# Arduino_Zero.net
KiCad netlist of a schematic drawn in EAGLE
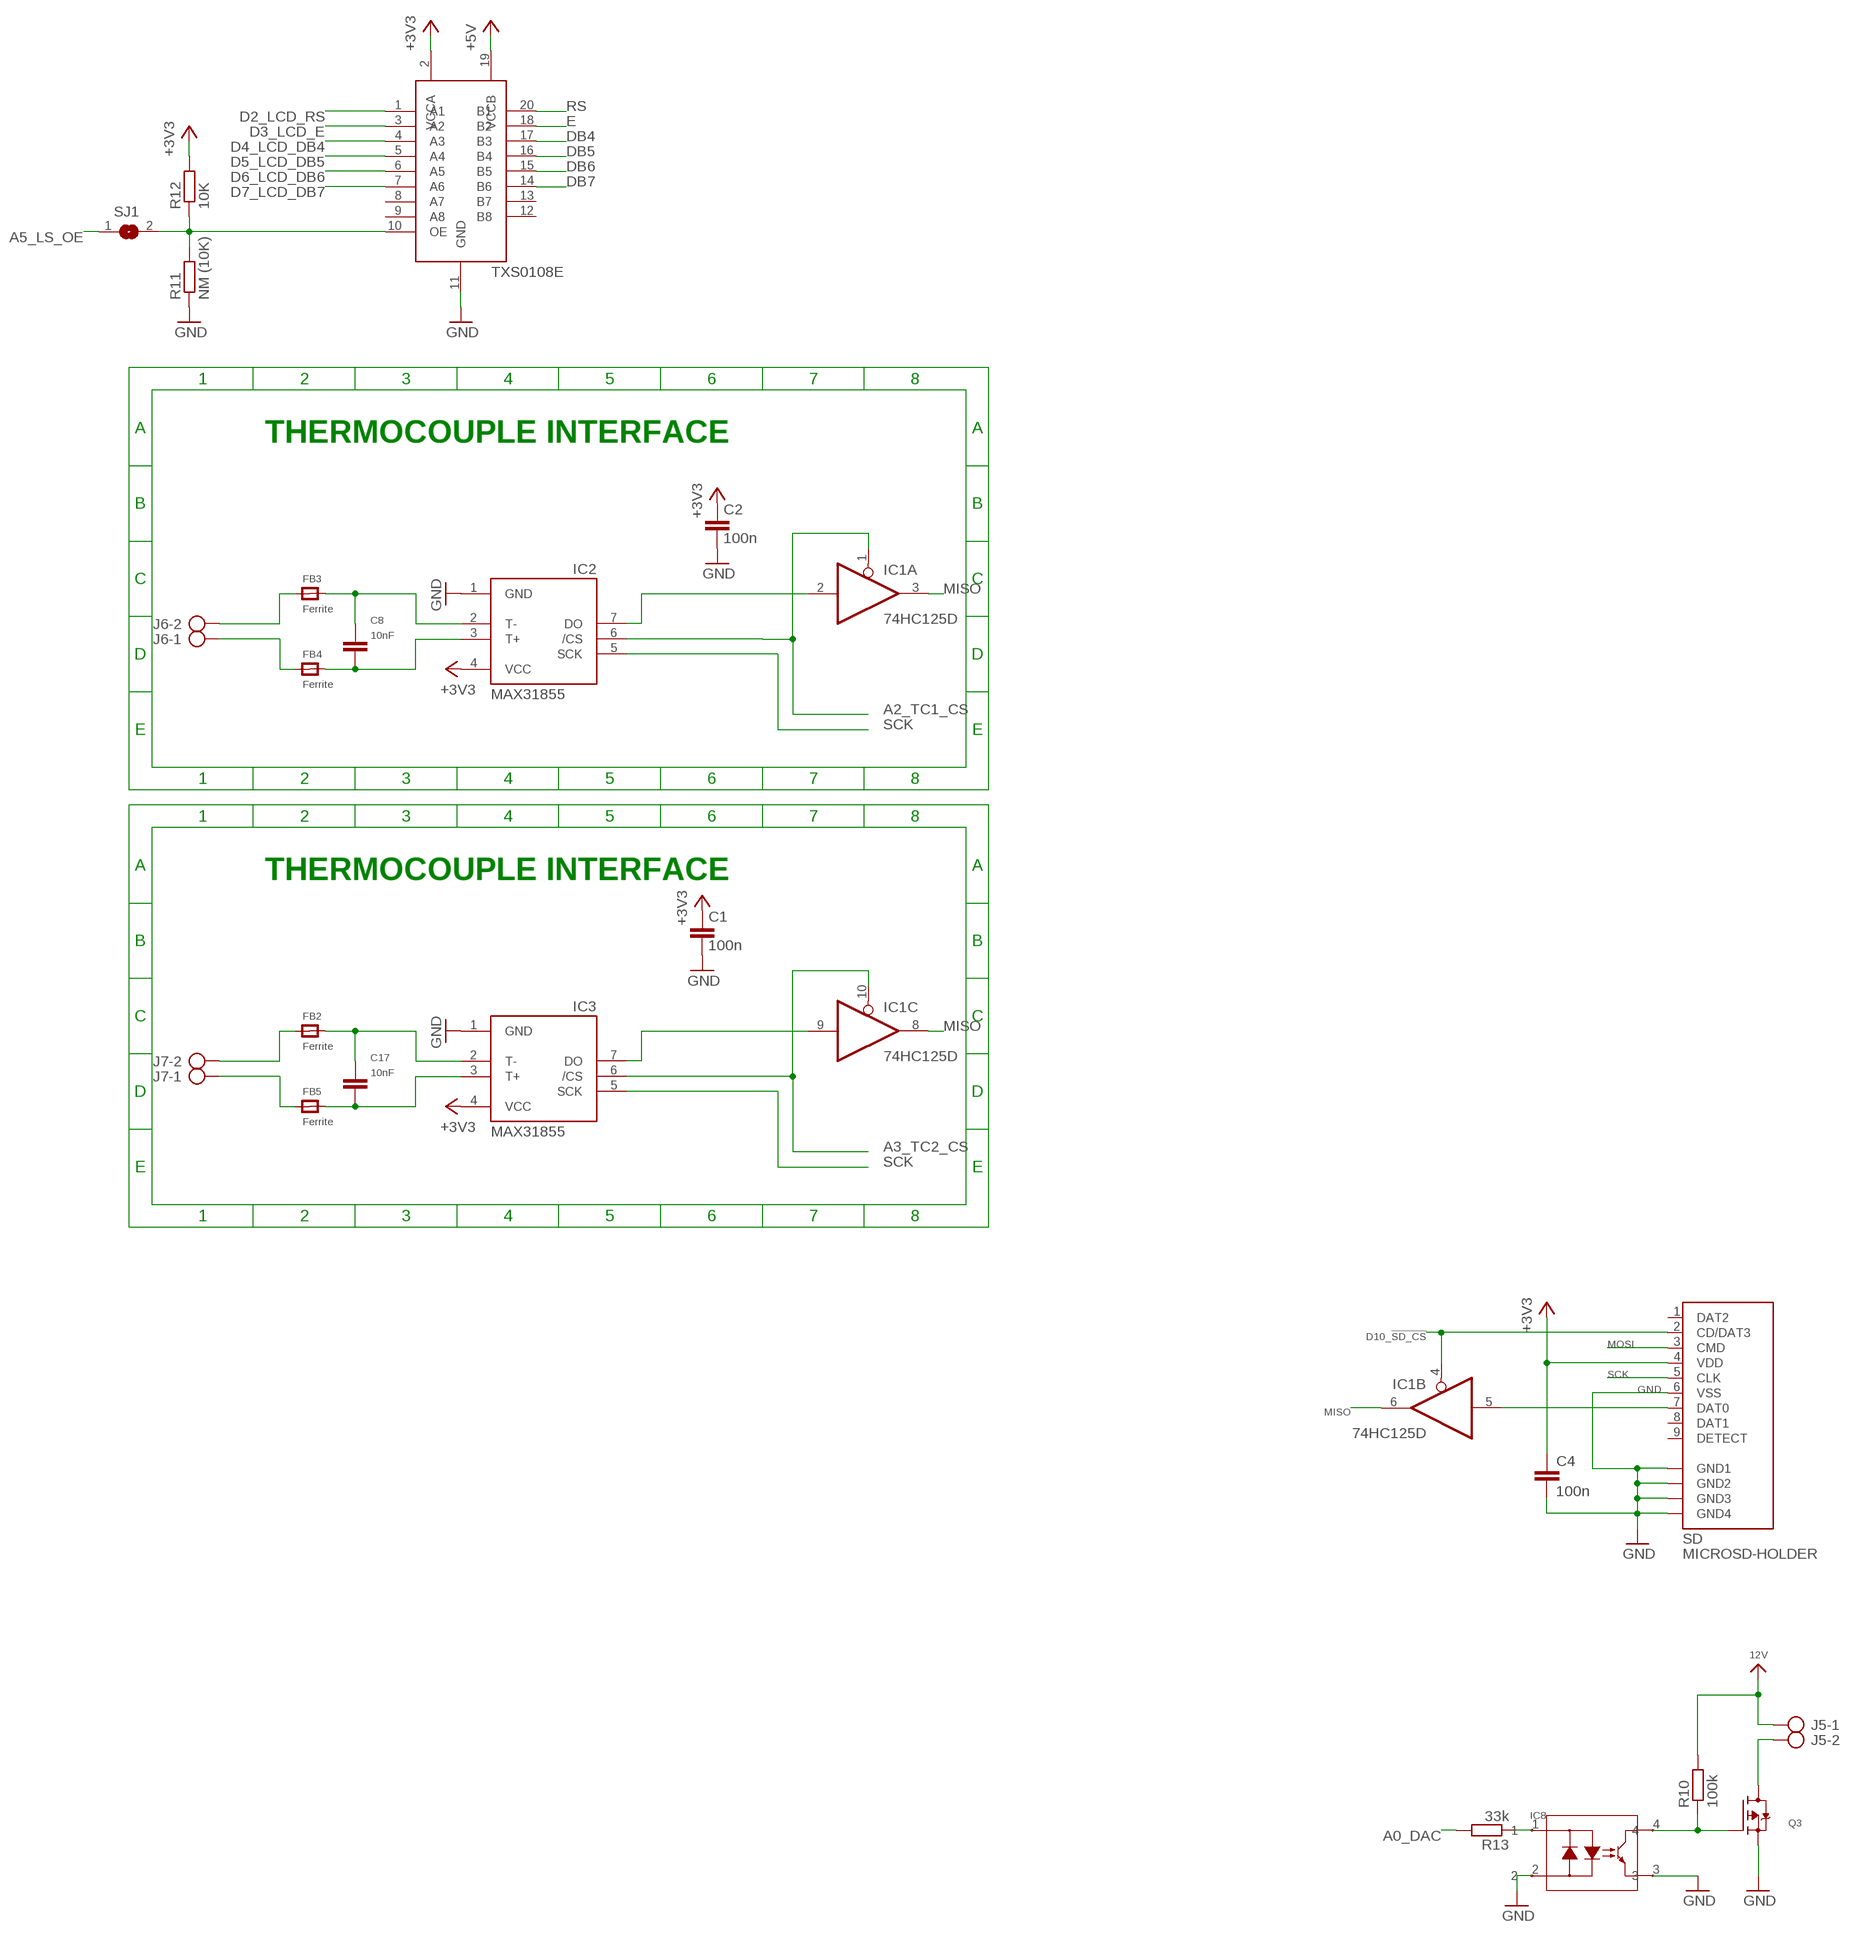
[diagram p0: schematic, sheet 1, part 1 of 2]
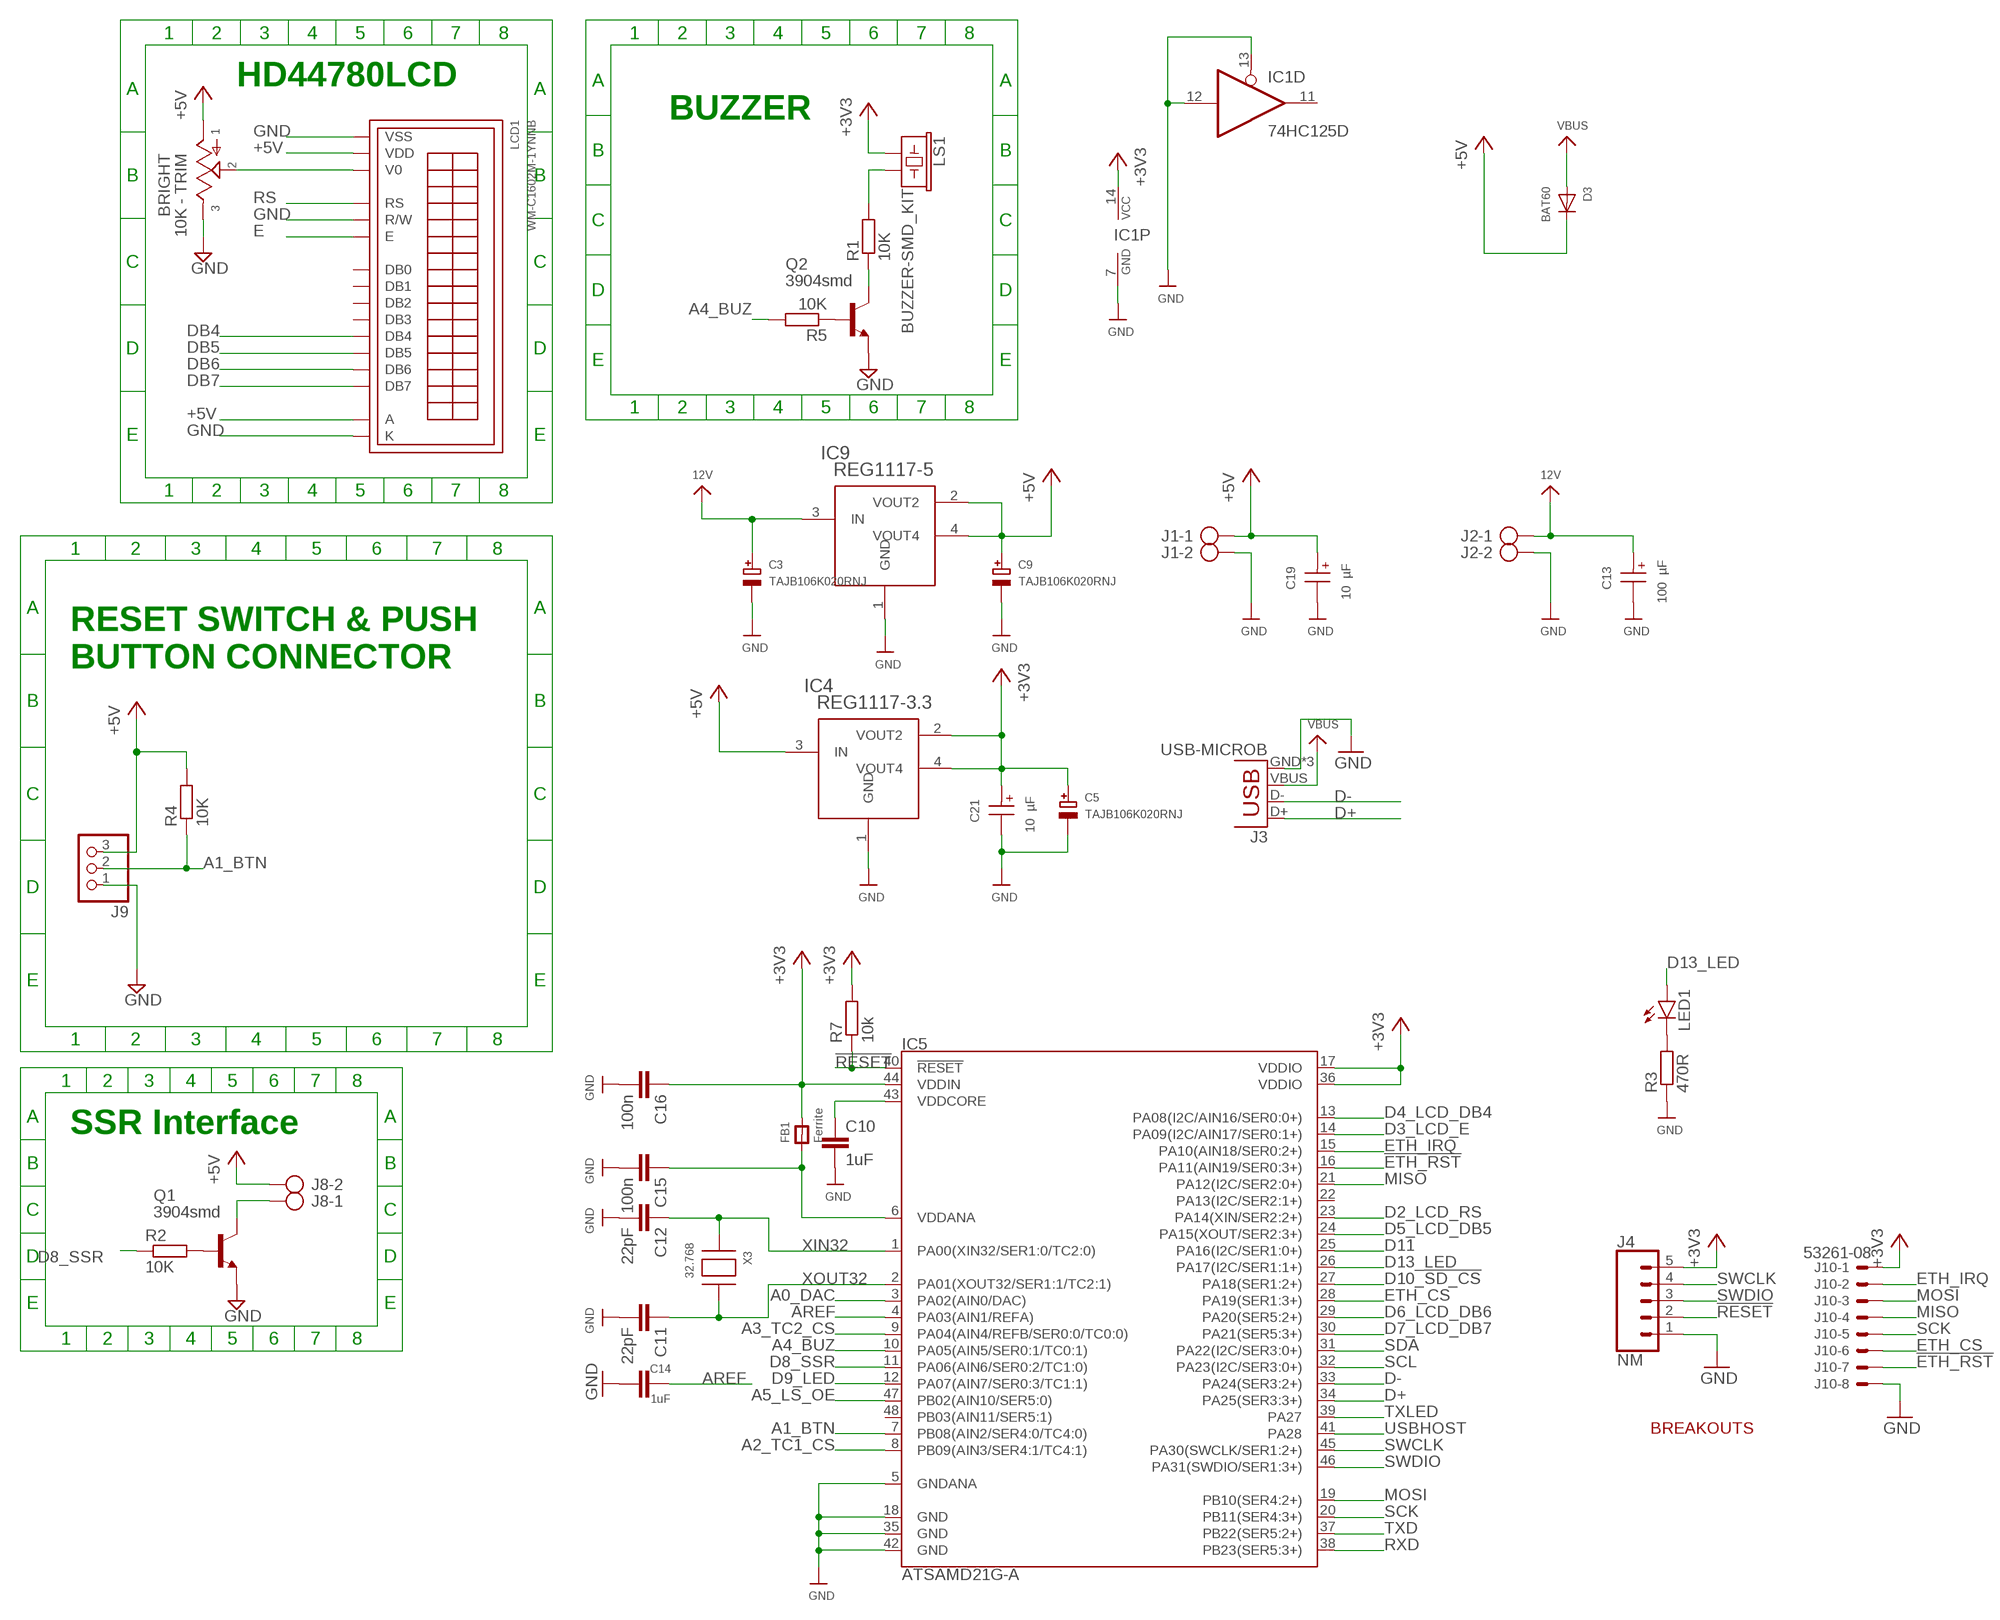
[diagram p1: schematic, sheet 1, part 2 of 2]

(export (version "E")
  (design (tool "Eeschema 10.0.6"))
  (components
    (comp (ref "BRIGHT")
      (value "10K - TRIM")
      (footprint "eagle-import:B25P")
      (libsource (lib "eagle-import") (part "POTTRIM"))
    )
    (comp (ref "C1")
      (value "100n")
      (footprint "eagle-import:C0603K")
      (libsource (lib "eagle-import") (part "C-EUC0603K"))
    )
    (comp (ref "C2")
      (value "100n")
      (footprint "eagle-import:C0603K")
      (libsource (lib "eagle-import") (part "C-EUC0603K"))
    )
    (comp (ref "C3")
      (value "TAJB106K020RNJ")
      (footprint "eagle-import:CAPMP3528X210N")
      (libsource (lib "eagle-import") (part "CAP_TANTALUM"))
    )
    (comp (ref "C4")
      (value "100n")
      (footprint "eagle-import:C0603K")
      (libsource (lib "eagle-import") (part "C-EUC0603K"))
    )
    (comp (ref "C5")
      (value "TAJB106K020RNJ")
      (footprint "eagle-import:CAPMP3528X210N")
      (libsource (lib "eagle-import") (part "CAP_TANTALUM"))
    )
    (comp (ref "C8")
      (value "10nF")
      (footprint "eagle-import:C0603K")
      (libsource (lib "eagle-import") (part "C-EUC0603K"))
    )
    (comp (ref "C9")
      (value "TAJB106K020RNJ")
      (footprint "eagle-import:CAPMP3528X210N")
      (libsource (lib "eagle-import") (part "CAP_TANTALUM"))
    )
    (comp (ref "C10")
      (value "1uF")
      (footprint "eagle-import:C0603K")
      (libsource (lib "eagle-import") (part "C-EUC0603K"))
    )
    (comp (ref "C11")
      (value "22pF")
      (footprint "eagle-import:C0603K")
      (libsource (lib "eagle-import") (part "C-EUC0603K"))
    )
    (comp (ref "C12")
      (value "22pF")
      (footprint "eagle-import:C0603K")
      (libsource (lib "eagle-import") (part "C-EUC0603K"))
    )
    (comp (ref "C13")
      (value "100 µF")
      (footprint "eagle-import:WCAP-ASLI_6.3X7.7(DXL)")
      (libsource (lib "eagle-import") (part "WCAP-ASLI_6.3X7.7_865080545012"))
    )
    (comp (ref "C14")
      (value "1uF")
      (footprint "eagle-import:C0603K")
      (libsource (lib "eagle-import") (part "C-EUC0603K"))
    )
    (comp (ref "C15")
      (value "100n")
      (footprint "eagle-import:C0603K")
      (libsource (lib "eagle-import") (part "C-EUC0603K"))
    )
    (comp (ref "C16")
      (value "100n")
      (footprint "eagle-import:C0603K")
      (libsource (lib "eagle-import") (part "C-EUC0603K"))
    )
    (comp (ref "C17")
      (value "10nF")
      (footprint "eagle-import:C0603K")
      (libsource (lib "eagle-import") (part "C-EUC0603K"))
    )
    (comp (ref "C19")
      (value "10 µF")
      (footprint "eagle-import:WCAP-ASLI_4X5.5(DXL)")
      (libsource (lib "eagle-import") (part "WCAP-ASLI_4X5.5_865080340001"))
    )
    (comp (ref "C21")
      (value "10 µF")
      (footprint "eagle-import:WCAP-ASLI_4X5.5(DXL)")
      (libsource (lib "eagle-import") (part "WCAP-ASLI_4X5.5_865080340001"))
    )
    (comp (ref "D3")
      (value "BAT60")
      (footprint "eagle-import:SOD323")
      (libsource (lib "eagle-import") (part "DIODESOD-323-3D"))
    )
    (comp (ref "FB1")
      (value "Ferrite")
      (footprint "eagle-import:BEADC3216X100N")
      (libsource (lib "eagle-import") (part "FERRITEBEAD"))
    )
    (comp (ref "FB2")
      (value "Ferrite")
      (footprint "eagle-import:BEADC3216X100N")
      (libsource (lib "eagle-import") (part "FERRITEBEAD"))
    )
    (comp (ref "FB3")
      (value "Ferrite")
      (footprint "eagle-import:BEADC3216X100N")
      (libsource (lib "eagle-import") (part "FERRITEBEAD"))
    )
    (comp (ref "FB4")
      (value "Ferrite")
      (footprint "eagle-import:BEADC3216X100N")
      (libsource (lib "eagle-import") (part "FERRITEBEAD"))
    )
    (comp (ref "FB5")
      (value "Ferrite")
      (footprint "eagle-import:BEADC3216X100N")
      (libsource (lib "eagle-import") (part "FERRITEBEAD"))
    )
    (comp (ref "IC1")
      (value "74HC125D")
      (footprint "eagle-import:SO14")
      (libsource (lib "eagle-import") (part "74125DHC"))
    )
    (comp (ref "IC2")
      (value "MAX31855")
      (footprint "eagle-import:SO08")
      (libsource (lib "eagle-import") (part "MAX6675"))
    )
    (comp (ref "IC3")
      (value "MAX31855")
      (footprint "eagle-import:SO08")
      (libsource (lib "eagle-import") (part "MAX6675"))
    )
    (comp (ref "IC4")
      (value "REG1117-3.3")
      (footprint "eagle-import:DCY0004A_N")
      (fields
        (field (name "MANUFACTURER_PART_NUMBER") "TLV1117-33CDCYR")
        (field (name "COPYRIGHT") "Copyright (C) 2022 Ultra Librarian. All rights reserved.")
      )
      (libsource (lib "eagle-import") (part "REG1117-5"))
    )
    (comp (ref "IC5")
      (value "ATSAMD21G-A")
      (footprint "eagle-import:TQFP-48")
      (libsource (lib "eagle-import") (part "ATSAMD21G-A"))
    )
    (comp (ref "IC7")
      (value "TXS0108E")
      (footprint "eagle-import:TSSOP20")
      (libsource (lib "eagle-import") (part "TXS0108E"))
    )
    (comp (ref "IC8")
      (value "TLP283")
      (footprint "eagle-import:SO4_TOS")
      (fields
        (field (name "MANUFACTURER_PART_NUMBER") "TLP292")
        (field (name "COPYRIGHT") "Copyright (C) 2022 Ultra Librarian. All rights reserved.")
      )
      (libsource (lib "eagle-import") (part "TLP292"))
    )
    (comp (ref "IC9")
      (value "REG1117-5")
      (footprint "eagle-import:DCY0004A_N")
      (fields
        (field (name "MANUFACTURER_PART_NUMBER") "TLV1117-33CDCYR")
        (field (name "COPYRIGHT") "Copyright (C) 2022 Ultra Librarian. All rights reserved.")
      )
      (libsource (lib "eagle-import") (part "REG1117-5"))
    )
    (comp (ref "J1")
      (value "AK500/2ASD")
      (footprint "eagle-import:AK500_2")
      (libsource (lib "eagle-import") (part "AK500/2ASD"))
    )
    (comp (ref "J2")
      (value "AK500/2ASD")
      (footprint "eagle-import:AK500_2")
      (libsource (lib "eagle-import") (part "AK500/2ASD"))
    )
    (comp (ref "J3")
      (value "USB-MICROB")
      (footprint "eagle-import:USB-MICROB")
      (libsource (lib "eagle-import") (part "USB-MICROB"))
    )
    (comp (ref "J4")
      (value "NM")
      (footprint "eagle-import:1X05_1.27MM")
      (libsource (lib "eagle-import") (part "CONN_051.27MM"))
    )
    (comp (ref "J5")
      (value "AK500/2ASD")
      (footprint "eagle-import:AK500_2")
      (libsource (lib "eagle-import") (part "AK500/2ASD"))
    )
    (comp (ref "J6")
      (value "AK500/2ASD")
      (footprint "eagle-import:AK500_2")
      (libsource (lib "eagle-import") (part "AK500/2ASD"))
    )
    (comp (ref "J7")
      (value "AK500/2ASD")
      (footprint "eagle-import:AK500_2")
      (libsource (lib "eagle-import") (part "AK500/2ASD"))
    )
    (comp (ref "J8")
      (value "AK500/2ASD")
      (footprint "eagle-import:AK500_2")
      (libsource (lib "eagle-import") (part "AK500/2ASD"))
    )
    (comp (ref "J9")
      (value "PINHD-1X3")
      (footprint "eagle-import:1X03")
      (libsource (lib "eagle-import") (part "PINHD-1X3"))
    )
    (comp (ref "J10")
      (value "53261-08")
      (footprint "eagle-import:53261-08")
      (fields (field (name "MF") "MOLEX"))
      (libsource (lib "eagle-import") (part "53?-08261"))
    )
    (comp (ref "LCD1")
      (value "WM-C1602M-1YNNB")
      (footprint "eagle-import:LCD_2")
      (libsource (lib "eagle-import") (part "WM-C1602M-1YNNB"))
    )
    (comp (ref "LED1")
      (value "LEDCHIPLED_0805")
      (footprint "eagle-import:CHIPLED_0805")
      (libsource (lib "eagle-import") (part "LEDCHIPLED_0805"))
    )
    (comp (ref "LS1")
      (value "BUZZER-SMD_KIT")
      (footprint "eagle-import:BUZZER-CCV-KIT")
      (libsource (lib "eagle-import") (part "BUZZER-SMD_KIT"))
    )
    (comp (ref "Q1")
      (value "3904smd")
      (footprint "eagle-import:SOT23-BEC")
      (libsource (lib "eagle-import") (part "BC850SMD"))
    )
    (comp (ref "Q2")
      (value "3904smd")
      (footprint "eagle-import:SOT23-BEC")
      (libsource (lib "eagle-import") (part "BC850SMD"))
    )
    (comp (ref "Q3")
      (value "MOSFET-PWIDE")
      (footprint "eagle-import:SOT23-WIDE")
      (libsource (lib "eagle-import") (part "MOSFET-PWIDE"))
    )
    (comp (ref "R1")
      (value "10K")
      (footprint "eagle-import:R0603")
      (libsource (lib "eagle-import") (part "R-EU_R0603"))
    )
    (comp (ref "R2")
      (value "10K")
      (footprint "eagle-import:R0603")
      (libsource (lib "eagle-import") (part "R-EU_R0603"))
    )
    (comp (ref "R3")
      (value "470R")
      (footprint "eagle-import:R0603")
      (libsource (lib "eagle-import") (part "R-EU_R0603"))
    )
    (comp (ref "R4")
      (value "10K")
      (footprint "eagle-import:R0603")
      (libsource (lib "eagle-import") (part "R-EU_R0603"))
    )
    (comp (ref "R5")
      (value "10K")
      (footprint "eagle-import:R0603")
      (libsource (lib "eagle-import") (part "R-EU_R0603"))
    )
    (comp (ref "R7")
      (value "10k")
      (footprint "eagle-import:R0603")
      (libsource (lib "eagle-import") (part "R-EU_R0603"))
    )
    (comp (ref "R10")
      (value "100k")
      (footprint "eagle-import:R0603")
      (libsource (lib "eagle-import") (part "R-EU_R0603"))
    )
    (comp (ref "R11")
      (value "NM (10K)")
      (footprint "eagle-import:R0603")
      (libsource (lib "eagle-import") (part "R-EU_R0603"))
    )
    (comp (ref "R12")
      (value "10K")
      (footprint "eagle-import:R0603")
      (libsource (lib "eagle-import") (part "R-EU_R0603"))
    )
    (comp (ref "R13")
      (value "33k")
      (footprint "eagle-import:R0603")
      (libsource (lib "eagle-import") (part "R-EU_R0603"))
    )
    (comp (ref "SD")
      (value "MICROSD-HOLDER")
      (footprint "eagle-import:MICROSD-HOLDER-ALIEX")
      (libsource (lib "eagle-import") (part "MICROSD-HOLDER"))
    )
    (comp (ref "SJ1") (value "SJ") (footprint "eagle-import:SJ") (libsource (lib "eagle-import") (part "SJ")))
    (comp (ref "X3")
      (value "32.768")
      (footprint "eagle-import:XTAL3215")
      (libsource (lib "eagle-import") (part "XTAL-3.2X1.5"))
    )
  )
  (nets
    (net (code "1") (name "+3V3") (class "Default")
      (node (ref "C1") (pin "1") (pinfunction "1_1") (pintype "passive"))
      (node (ref "C16") (pin "1") (pinfunction "1_1") (pintype "passive"))
      (node (ref "C2") (pin "1") (pinfunction "1_1") (pintype "passive"))
      (node (ref "C21") (pin "1") (pinfunction "+_1") (pintype "passive"))
      (node (ref "C4") (pin "1") (pinfunction "1_1") (pintype "passive"))
      (node (ref "C5") (pin "1") (pinfunction "+_1") (pintype "passive"))
      (node (ref "FB1") (pin "2") (pinfunction "P$2_2") (pintype "passive"))
      (node (ref "IC1") (pin "14") (pinfunction "VCC_14") (pintype "power_in"))
      (node (ref "IC2") (pin "4") (pinfunction "VCC_4") (pintype "power_in"))
      (node (ref "IC3") (pin "4") (pinfunction "VCC_4") (pintype "power_in"))
      (node (ref "IC4") (pin "2") (pinfunction "VOUT2_2") (pintype "power_in"))
      (node (ref "IC4") (pin "4") (pinfunction "VOUT4_4") (pintype "power_in"))
      (node (ref "IC5") (pin "17") (pinfunction "VDDIO_17") (pintype "bidirectional"))
      (node (ref "IC5") (pin "36") (pinfunction "VDDIO_36") (pintype "bidirectional"))
      (node (ref "IC5") (pin "44") (pinfunction "VDDIN_44") (pintype "bidirectional"))
      (node (ref "IC7") (pin "2") (pinfunction "VCCA_2") (pintype "bidirectional"))
      (node (ref "J10") (pin "1") (pinfunction "S_1") (pintype "passive"))
      (node (ref "J4") (pin "5") (pinfunction "5_5") (pintype "passive"))
      (node (ref "LS1") (pin "+") (pinfunction "1_+") (pintype "passive"))
      (node (ref "R12") (pin "2") (pinfunction "2_2") (pintype "passive"))
      (node (ref "R7") (pin "2") (pinfunction "2_2") (pintype "passive"))
      (node (ref "SD") (pin "4") (pinfunction "VDD_4") (pintype "bidirectional"))
    )
    (net (code "2") (name "+5V") (class "Default")
      (node (ref "BRIGHT") (pin "1") (pinfunction "1_1") (pintype "passive"))
      (node (ref "C19") (pin "1") (pinfunction "+_1") (pintype "passive"))
      (node (ref "C9") (pin "1") (pinfunction "+_1") (pintype "passive"))
      (node (ref "D3") (pin "1") (pinfunction "C_1") (pintype "passive"))
      (node (ref "IC4") (pin "3") (pinfunction "IN_3") (pintype "power_in"))
      (node (ref "IC7") (pin "19") (pinfunction "VCCB_19") (pintype "bidirectional"))
      (node (ref "IC9") (pin "2") (pinfunction "VOUT2_2") (pintype "power_in"))
      (node (ref "IC9") (pin "4") (pinfunction "VOUT4_4") (pintype "power_in"))
      (node (ref "J1") (pin "1") (pinfunction "KL_1") (pintype "passive"))
      (node (ref "J8") (pin "2") (pinfunction "KL_2") (pintype "passive"))
      (node (ref "J9") (pin "3") (pinfunction "3_3") (pintype "passive"))
      (node (ref "LCD1") (pin "15") (pinfunction "A_15") (pintype "bidirectional"))
      (node (ref "LCD1") (pin "2") (pinfunction "VDD_2") (pintype "bidirectional"))
      (node (ref "R4") (pin "2") (pinfunction "2_2") (pintype "passive"))
    )
    (net (code "3") (name "/A0_DAC") (class "Default")
      (node (ref "IC5") (pin "3") (pinfunction "PA02(AIN0/DAC)_3") (pintype "bidirectional"))
      (node (ref "R13") (pin "2") (pinfunction "2_2") (pintype "passive"))
    )
    (net (code "4") (name "/A1_BTN") (class "Default")
      (node (ref "IC5") (pin "7") (pinfunction "PB08(AIN2/SER4:0/TC4:0)_7") (pintype "bidirectional"))
      (node (ref "J9") (pin "2") (pinfunction "2_2") (pintype "passive"))
      (node (ref "R4") (pin "1") (pinfunction "1_1") (pintype "passive"))
    )
    (net (code "5") (name "/A2_TC1_CS") (class "Default")
      (node (ref "IC1") (pin "1") (pinfunction "OE_1") (pintype "input"))
      (node (ref "IC2") (pin "6") (pinfunction "/CS_6") (pintype "input"))
      (node (ref "IC5") (pin "8") (pinfunction "PB09(AIN3/SER4:1/TC4:1)_8") (pintype "bidirectional"))
    )
    (net (code "6") (name "/A3_TC2_CS") (class "Default")
      (node (ref "IC1") (pin "10") (pinfunction "OE_10") (pintype "input"))
      (node (ref "IC3") (pin "6") (pinfunction "/CS_6") (pintype "input"))
      (node (ref "IC5") (pin "9") (pinfunction "PA04(AIN4/REFB/SER0:0/TC0:0)_9") (pintype "bidirectional"))
    )
    (net (code "7") (name "/A4_BUZ") (class "Default")
      (node (ref "IC5") (pin "10") (pinfunction "PA05(AIN5/SER0:1/TC0:1)_10") (pintype "bidirectional"))
      (node (ref "R5") (pin "2") (pinfunction "2_2") (pintype "passive"))
    )
    (net (code "8") (name "/A5_LS_OE") (class "Default")
      (node (ref "IC5") (pin "47") (pinfunction "PB02(AIN10/SER5:0)_47") (pintype "bidirectional"))
      (node (ref "SJ1") (pin "1") (pinfunction "1_1") (pintype "passive"))
    )
    (net (code "9") (name "/AREF") (class "Default")
      (node (ref "C14") (pin "1") (pinfunction "1_1") (pintype "passive"))
      (node (ref "IC5") (pin "4") (pinfunction "PA03(AIN1/REFA)_4") (pintype "bidirectional"))
    )
    (net (code "10") (name "/D+") (class "Default")
      (node (ref "IC5") (pin "34") (pinfunction "PA25(SER3:3+)_34") (pintype "bidirectional"))
      (node (ref "J3") (pin "D+") (pinfunction "D+_D+") (pintype "bidirectional"))
    )
    (net (code "11") (name "/D-") (class "Default")
      (node (ref "IC5") (pin "33") (pinfunction "PA24(SER3:2+)_33") (pintype "bidirectional"))
      (node (ref "J3") (pin "D-") (pinfunction "D-_D-") (pintype "bidirectional"))
    )
    (net (code "12") (name "/D2_LCD_RS") (class "Default")
      (node (ref "IC5") (pin "23") (pinfunction "PA14(XIN/SER2:2+)_23") (pintype "bidirectional"))
      (node (ref "IC7") (pin "1") (pinfunction "A1_1") (pintype "bidirectional"))
    )
    (net (code "13") (name "/D3_LCD_E") (class "Default")
      (node (ref "IC5") (pin "14") (pinfunction "PA09(I2C/AIN17/SER0:1+)_14") (pintype "bidirectional"))
      (node (ref "IC7") (pin "3") (pinfunction "A2_3") (pintype "bidirectional"))
    )
    (net (code "14") (name "/D4_LCD_DB4") (class "Default")
      (node (ref "IC5") (pin "13") (pinfunction "PA08(I2C/AIN16/SER0:0+)_13") (pintype "bidirectional"))
      (node (ref "IC7") (pin "4") (pinfunction "A3_4") (pintype "bidirectional"))
    )
    (net (code "15") (name "/D5_LCD_DB5") (class "Default")
      (node (ref "IC5") (pin "24") (pinfunction "PA15(XOUT/SER2:3+)_24") (pintype "bidirectional"))
      (node (ref "IC7") (pin "5") (pinfunction "A4_5") (pintype "bidirectional"))
    )
    (net (code "16") (name "/D6_LCD_DB6") (class "Default")
      (node (ref "IC5") (pin "29") (pinfunction "PA20(SER5:2+)_29") (pintype "bidirectional"))
      (node (ref "IC7") (pin "6") (pinfunction "A5_6") (pintype "bidirectional"))
    )
    (net (code "17") (name "/D7_LCD_DB7") (class "Default")
      (node (ref "IC5") (pin "30") (pinfunction "PA21(SER5:3+)_30") (pintype "bidirectional"))
      (node (ref "IC7") (pin "7") (pinfunction "A6_7") (pintype "bidirectional"))
    )
    (net (code "18") (name "/D8_SSR") (class "Default")
      (node (ref "IC5") (pin "11") (pinfunction "PA06(AIN6/SER0:2/TC1:0)_11") (pintype "bidirectional"))
      (node (ref "R2") (pin "1") (pinfunction "1_1") (pintype "passive"))
    )
    (net (code "19") (name "/D9_LED") (class "Default")
      (node (ref "IC5") (pin "12") (pinfunction "PA07(AIN7/SER0:3/TC1:1)_12") (pintype "bidirectional"))
    )
    (net (code "20") (name "/D10_~{SD_CS}") (class "Default")
      (node (ref "IC1") (pin "4") (pinfunction "OE_4") (pintype "input"))
      (node (ref "IC5") (pin "27") (pinfunction "PA18(SER1:2+)_27") (pintype "bidirectional"))
      (node (ref "SD") (pin "2") (pinfunction "CD/DAT3_2") (pintype "bidirectional"))
    )
    (net (code "21") (name "/D11") (class "Default")
      (node (ref "IC5") (pin "25") (pinfunction "PA16(I2C/SER1:0+)_25") (pintype "bidirectional"))
    )
    (net (code "22") (name "/D13_LED") (class "Default")
      (node (ref "IC5") (pin "26") (pinfunction "PA17(I2C/SER1:1+)_26") (pintype "bidirectional"))
      (node (ref "LED1") (pin "A") (pinfunction "A_A") (pintype "passive"))
    )
    (net (code "23") (name "/DB4") (class "Default")
      (node (ref "IC7") (pin "17") (pinfunction "B3_17") (pintype "bidirectional"))
      (node (ref "LCD1") (pin "11") (pinfunction "DB4_11") (pintype "bidirectional"))
    )
    (net (code "24") (name "/DB5") (class "Default")
      (node (ref "IC7") (pin "16") (pinfunction "B4_16") (pintype "bidirectional"))
      (node (ref "LCD1") (pin "12") (pinfunction "DB5_12") (pintype "bidirectional"))
    )
    (net (code "25") (name "/DB6") (class "Default")
      (node (ref "IC7") (pin "15") (pinfunction "B5_15") (pintype "bidirectional"))
      (node (ref "LCD1") (pin "13") (pinfunction "DB6_13") (pintype "bidirectional"))
    )
    (net (code "26") (name "/DB7") (class "Default")
      (node (ref "IC7") (pin "14") (pinfunction "B6_14") (pintype "bidirectional"))
      (node (ref "LCD1") (pin "14") (pinfunction "DB7_14") (pintype "bidirectional"))
    )
    (net (code "27") (name "/E") (class "Default")
      (node (ref "IC7") (pin "18") (pinfunction "B2_18") (pintype "bidirectional"))
      (node (ref "LCD1") (pin "6") (pinfunction "E_6") (pintype "bidirectional"))
    )
    (net (code "28") (name "/ETH_CS") (class "Default")
      (node (ref "IC5") (pin "28") (pinfunction "PA19(SER1:3+)_28") (pintype "bidirectional"))
      (node (ref "J10") (pin "6") (pinfunction "S_6") (pintype "passive"))
    )
    (net (code "29") (name "/ETH_IRQ") (class "Default")
      (node (ref "IC5") (pin "15") (pinfunction "PA10(AIN18/SER0:2+)_15") (pintype "bidirectional"))
      (node (ref "J10") (pin "2") (pinfunction "S_2") (pintype "passive"))
    )
    (net (code "30") (name "/MISO") (class "Default")
      (node (ref "IC1") (pin "3") (pinfunction "O_3") (pintype "tri_state"))
      (node (ref "IC1") (pin "6") (pinfunction "O_6") (pintype "tri_state"))
      (node (ref "IC1") (pin "8") (pinfunction "O_8") (pintype "tri_state"))
      (node (ref "IC5") (pin "21") (pinfunction "PA12(I2C/SER2:0+)_21") (pintype "bidirectional"))
      (node (ref "J10") (pin "4") (pinfunction "S_4") (pintype "passive"))
    )
    (net (code "31") (name "/MOSI") (class "Default")
      (node (ref "IC5") (pin "19") (pinfunction "PB10(SER4:2+)_19") (pintype "bidirectional"))
      (node (ref "J10") (pin "3") (pinfunction "S_3") (pintype "passive"))
      (node (ref "SD") (pin "3") (pinfunction "CMD_3") (pintype "bidirectional"))
    )
    (net (code "32") (name "/RS") (class "Default")
      (node (ref "IC7") (pin "20") (pinfunction "B1_20") (pintype "bidirectional"))
      (node (ref "LCD1") (pin "4") (pinfunction "RS_4") (pintype "bidirectional"))
    )
    (net (code "33") (name "/RXD") (class "Default")
      (node (ref "IC5") (pin "38") (pinfunction "PB23(SER5:3+)_38") (pintype "bidirectional"))
    )
    (net (code "34") (name "/SCK") (class "Default")
      (node (ref "IC2") (pin "5") (pinfunction "SCK_5") (pintype "input"))
      (node (ref "IC3") (pin "5") (pinfunction "SCK_5") (pintype "input"))
      (node (ref "IC5") (pin "20") (pinfunction "PB11(SER4:3+)_20") (pintype "bidirectional"))
      (node (ref "J10") (pin "5") (pinfunction "S_5") (pintype "passive"))
      (node (ref "SD") (pin "5") (pinfunction "CLK_5") (pintype "bidirectional"))
    )
    (net (code "35") (name "/SCL") (class "Default")
      (node (ref "IC5") (pin "32") (pinfunction "PA23(I2C/SER3:0+)_32") (pintype "bidirectional"))
    )
    (net (code "36") (name "/SDA") (class "Default")
      (node (ref "IC5") (pin "31") (pinfunction "PA22(I2C/SER3:0+)_31") (pintype "bidirectional"))
    )
    (net (code "37") (name "/SWCLK") (class "Default")
      (node (ref "IC5") (pin "45") (pinfunction "PA30(SWCLK/SER1:2+)_45") (pintype "bidirectional"))
      (node (ref "J4") (pin "4") (pinfunction "4_4") (pintype "passive"))
    )
    (net (code "38") (name "/SWDIO") (class "Default")
      (node (ref "IC5") (pin "46") (pinfunction "PA31(SWDIO/SER1:3+)_46") (pintype "bidirectional"))
      (node (ref "J4") (pin "3") (pinfunction "3_3") (pintype "passive"))
    )
    (net (code "39") (name "/TXD") (class "Default")
      (node (ref "IC5") (pin "37") (pinfunction "PB22(SER5:2+)_37") (pintype "bidirectional"))
    )
    (net (code "40") (name "/TXLED") (class "Default")
      (node (ref "IC5") (pin "39") (pinfunction "PA27_39") (pintype "bidirectional"))
    )
    (net (code "41") (name "/USBHOST") (class "Default")
      (node (ref "IC5") (pin "41") (pinfunction "PA28_41") (pintype "bidirectional"))
    )
    (net (code "42") (name "/XIN32") (class "Default")
      (node (ref "C12") (pin "1") (pinfunction "1_1") (pintype "passive"))
      (node (ref "IC5") (pin "1") (pinfunction "PA00(XIN32/SER1:0/TC2:0)_1") (pintype "bidirectional"))
      (node (ref "X3") (pin "P$1") (pinfunction "P$1_P$1") (pintype "bidirectional"))
    )
    (net (code "43") (name "/XOUT32") (class "Default")
      (node (ref "C11") (pin "1") (pinfunction "1_1") (pintype "passive"))
      (node (ref "IC5") (pin "2") (pinfunction "PA01(XOUT32/SER1:1/TC2:1)_2") (pintype "bidirectional"))
      (node (ref "X3") (pin "P$2") (pinfunction "P$2_P$2") (pintype "bidirectional"))
    )
    (net (code "44") (name "/~{ETH_RST}") (class "Default")
      (node (ref "IC5") (pin "16") (pinfunction "PA11(AIN19/SER0:3+)_16") (pintype "bidirectional"))
      (node (ref "J10") (pin "7") (pinfunction "S_7") (pintype "passive"))
    )
    (net (code "45") (name "/~{RESET}") (class "Default")
      (node (ref "IC5") (pin "40") (pinfunction "~{RESET}_40") (pintype "bidirectional"))
      (node (ref "J4") (pin "2") (pinfunction "2_2") (pintype "passive"))
      (node (ref "R7") (pin "1") (pinfunction "1_1") (pintype "passive"))
    )
    (net (code "46") (name "12V") (class "Default")
      (node (ref "C13") (pin "1") (pinfunction "+_1") (pintype "passive"))
      (node (ref "C3") (pin "1") (pinfunction "+_1") (pintype "passive"))
      (node (ref "IC9") (pin "3") (pinfunction "IN_3") (pintype "power_in"))
      (node (ref "J2") (pin "1") (pinfunction "KL_1") (pintype "passive"))
      (node (ref "J5") (pin "1") (pinfunction "KL_1") (pintype "passive"))
      (node (ref "R10") (pin "2") (pinfunction "2_2") (pintype "passive"))
    )
    (net (code "47") (name "GND") (class "Default")
      (node (ref "BRIGHT") (pin "3") (pinfunction "3_3") (pintype "passive"))
      (node (ref "C1") (pin "2") (pinfunction "2_2") (pintype "passive"))
      (node (ref "C10") (pin "2") (pinfunction "2_2") (pintype "passive"))
      (node (ref "C11") (pin "2") (pinfunction "2_2") (pintype "passive"))
      (node (ref "C12") (pin "2") (pinfunction "2_2") (pintype "passive"))
      (node (ref "C13") (pin "2") (pinfunction "-_2") (pintype "passive"))
      (node (ref "C14") (pin "2") (pinfunction "2_2") (pintype "passive"))
      (node (ref "C15") (pin "2") (pinfunction "2_2") (pintype "passive"))
      (node (ref "C16") (pin "2") (pinfunction "2_2") (pintype "passive"))
      (node (ref "C19") (pin "2") (pinfunction "-_2") (pintype "passive"))
      (node (ref "C2") (pin "2") (pinfunction "2_2") (pintype "passive"))
      (node (ref "C21") (pin "2") (pinfunction "-_2") (pintype "passive"))
      (node (ref "C3") (pin "2") (pinfunction "-_2") (pintype "passive"))
      (node (ref "C4") (pin "2") (pinfunction "2_2") (pintype "passive"))
      (node (ref "C5") (pin "2") (pinfunction "-_2") (pintype "passive"))
      (node (ref "C9") (pin "2") (pinfunction "-_2") (pintype "passive"))
      (node (ref "IC1") (pin "12") (pinfunction "I_12") (pintype "input"))
      (node (ref "IC1") (pin "13") (pinfunction "OE_13") (pintype "input"))
      (node (ref "IC1") (pin "7") (pinfunction "GND_7") (pintype "power_in"))
      (node (ref "IC2") (pin "1") (pinfunction "GND_1") (pintype "power_in"))
      (node (ref "IC3") (pin "1") (pinfunction "GND_1") (pintype "power_in"))
      (node (ref "IC4") (pin "1") (pinfunction "GND_1") (pintype "power_in"))
      (node (ref "IC5") (pin "18") (pinfunction "GND_18") (pintype "bidirectional"))
      (node (ref "IC5") (pin "35") (pinfunction "GND_35") (pintype "bidirectional"))
      (node (ref "IC5") (pin "42") (pinfunction "GND_42") (pintype "bidirectional"))
      (node (ref "IC5") (pin "5") (pinfunction "GNDANA_5") (pintype "bidirectional"))
      (node (ref "IC7") (pin "11") (pinfunction "GND_11") (pintype "bidirectional"))
      (node (ref "IC8") (pin "2") (pinfunction "2_2") (pintype "passive"))
      (node (ref "IC8") (pin "3") (pinfunction "3_3") (pintype "passive"))
      (node (ref "IC9") (pin "1") (pinfunction "GND_1") (pintype "power_in"))
      (node (ref "J1") (pin "2") (pinfunction "KL_2") (pintype "passive"))
      (node (ref "J10") (pin "8") (pinfunction "S_8") (pintype "passive"))
      (node (ref "J2") (pin "2") (pinfunction "KL_2") (pintype "passive"))
      (node (ref "J3") (pin "GND") (pinfunction "GND_GND") (pintype "bidirectional"))
      (node (ref "J3") (pin "MT1") (pinfunction "GND_MT1") (pintype "bidirectional"))
      (node (ref "J3") (pin "MT2") (pinfunction "GND_MT2") (pintype "bidirectional"))
      (node (ref "J4") (pin "1") (pinfunction "1_1") (pintype "passive"))
      (node (ref "J9") (pin "1") (pinfunction "1_1") (pintype "passive"))
      (node (ref "LCD1") (pin "1") (pinfunction "VSS_1") (pintype "bidirectional"))
      (node (ref "LCD1") (pin "16") (pinfunction "K_16") (pintype "bidirectional"))
      (node (ref "LCD1") (pin "5") (pinfunction "R/W_5") (pintype "bidirectional"))
      (node (ref "Q1") (pin "E") (pinfunction "E_E") (pintype "passive"))
      (node (ref "Q2") (pin "E") (pinfunction "E_E") (pintype "passive"))
      (node (ref "Q3") (pin "2") (pinfunction "S_2") (pintype "passive"))
      (node (ref "R11") (pin "1") (pinfunction "1_1") (pintype "passive"))
      (node (ref "R3") (pin "1") (pinfunction "1_1") (pintype "passive"))
      (node (ref "SD") (pin "6") (pinfunction "VSS_6") (pintype "bidirectional"))
      (node (ref "SD") (pin "P$1") (pinfunction "GND1_P$1") (pintype "bidirectional"))
      (node (ref "SD") (pin "P$2") (pinfunction "GND2_P$2") (pintype "bidirectional"))
      (node (ref "SD") (pin "P$3") (pinfunction "GND3_P$3") (pintype "bidirectional"))
      (node (ref "SD") (pin "P$4") (pinfunction "GND4_P$4") (pintype "bidirectional"))
    )
    (net (code "48") (name "Net-(FB1-P$1)") (class "Default")
      (node (ref "C15") (pin "1") (pinfunction "1_1") (pintype "passive"))
      (node (ref "FB1") (pin "1") (pinfunction "P$1_1") (pintype "passive"))
      (node (ref "IC5") (pin "6") (pinfunction "VDDANA_6") (pintype "bidirectional"))
    )
    (net (code "49") (name "Net-(FB2-P$1)") (class "Default")
      (node (ref "FB2") (pin "1") (pinfunction "P$1_1") (pintype "passive"))
      (node (ref "J7") (pin "2") (pinfunction "KL_2") (pintype "passive"))
    )
    (net (code "50") (name "Net-(FB2-P$2)") (class "Default")
      (node (ref "C17") (pin "1") (pinfunction "1_1") (pintype "passive"))
      (node (ref "FB2") (pin "2") (pinfunction "P$2_2") (pintype "passive"))
      (node (ref "IC3") (pin "2") (pinfunction "T-_2") (pintype "input"))
    )
    (net (code "51") (name "Net-(FB3-P$1)") (class "Default")
      (node (ref "FB3") (pin "1") (pinfunction "P$1_1") (pintype "passive"))
      (node (ref "J6") (pin "2") (pinfunction "KL_2") (pintype "passive"))
    )
    (net (code "52") (name "Net-(FB3-P$2)") (class "Default")
      (node (ref "C8") (pin "1") (pinfunction "1_1") (pintype "passive"))
      (node (ref "FB3") (pin "2") (pinfunction "P$2_2") (pintype "passive"))
      (node (ref "IC2") (pin "2") (pinfunction "T-_2") (pintype "input"))
    )
    (net (code "53") (name "Net-(FB4-P$1)") (class "Default")
      (node (ref "FB4") (pin "1") (pinfunction "P$1_1") (pintype "passive"))
      (node (ref "J6") (pin "1") (pinfunction "KL_1") (pintype "passive"))
    )
    (net (code "54") (name "Net-(FB4-P$2)") (class "Default")
      (node (ref "C8") (pin "2") (pinfunction "2_2") (pintype "passive"))
      (node (ref "FB4") (pin "2") (pinfunction "P$2_2") (pintype "passive"))
      (node (ref "IC2") (pin "3") (pinfunction "T+_3") (pintype "input"))
    )
    (net (code "55") (name "Net-(FB5-P$1)") (class "Default")
      (node (ref "FB5") (pin "1") (pinfunction "P$1_1") (pintype "passive"))
      (node (ref "J7") (pin "1") (pinfunction "KL_1") (pintype "passive"))
    )
    (net (code "56") (name "Net-(FB5-P$2)") (class "Default")
      (node (ref "C17") (pin "2") (pinfunction "2_2") (pintype "passive"))
      (node (ref "FB5") (pin "2") (pinfunction "P$2_2") (pintype "passive"))
      (node (ref "IC3") (pin "3") (pinfunction "T+_3") (pintype "input"))
    )
    (net (code "57") (name "Net-(IC1A-I)") (class "Default")
      (node (ref "IC1") (pin "2") (pinfunction "I_2") (pintype "input"))
      (node (ref "IC2") (pin "7") (pinfunction "DO_7") (pintype "output"))
    )
    (net (code "58") (name "Net-(IC1B-I)") (class "Default")
      (node (ref "IC1") (pin "5") (pinfunction "I_5") (pintype "input"))
      (node (ref "SD") (pin "7") (pinfunction "DAT0_7") (pintype "bidirectional"))
    )
    (net (code "59") (name "Net-(IC1C-I)") (class "Default")
      (node (ref "IC1") (pin "9") (pinfunction "I_9") (pintype "input"))
      (node (ref "IC3") (pin "7") (pinfunction "DO_7") (pintype "output"))
    )
    (net (code "60") (name "Net-(IC5-VDDCORE)") (class "Default")
      (node (ref "C10") (pin "1") (pinfunction "1_1") (pintype "passive"))
      (node (ref "IC5") (pin "43") (pinfunction "VDDCORE_43") (pintype "bidirectional"))
    )
    (net (code "61") (name "Net-(IC7-OE)") (class "Default")
      (node (ref "IC7") (pin "10") (pinfunction "OE_10") (pintype "bidirectional"))
      (node (ref "R11") (pin "2") (pinfunction "2_2") (pintype "passive"))
      (node (ref "R12") (pin "1") (pinfunction "1_1") (pintype "passive"))
      (node (ref "SJ1") (pin "2") (pinfunction "2_2") (pintype "passive"))
    )
    (net (code "62") (name "Net-(IC8-Pad1)") (class "Default")
      (node (ref "IC8") (pin "1") (pinfunction "1_1") (pintype "passive"))
      (node (ref "R13") (pin "1") (pinfunction "1_1") (pintype "passive"))
    )
    (net (code "63") (name "Net-(J5B-KL)") (class "Default")
      (node (ref "J5") (pin "2") (pinfunction "KL_2") (pintype "passive"))
      (node (ref "Q3") (pin "3") (pinfunction "D_3") (pintype "passive"))
    )
    (net (code "64") (name "Net-(J8A-KL)") (class "Default")
      (node (ref "J8") (pin "1") (pinfunction "KL_1") (pintype "passive"))
      (node (ref "Q1") (pin "C") (pinfunction "C_C") (pintype "passive"))
    )
    (net (code "65") (name "Net-(LCD1-V0)") (class "Default")
      (node (ref "BRIGHT") (pin "2") (pinfunction "2_2") (pintype "passive"))
      (node (ref "LCD1") (pin "3") (pinfunction "V0_3") (pintype "bidirectional"))
    )
    (net (code "66") (name "Net-(LED1-PadC)") (class "Default")
      (node (ref "LED1") (pin "C") (pinfunction "C_C") (pintype "passive"))
      (node (ref "R3") (pin "2") (pinfunction "2_2") (pintype "passive"))
    )
    (net (code "67") (name "Net-(LS1-2)") (class "Default")
      (node (ref "LS1") (pin "-") (pinfunction "2_-") (pintype "passive"))
      (node (ref "R1") (pin "2") (pinfunction "2_2") (pintype "passive"))
    )
    (net (code "68") (name "Net-(Q1-PadB)") (class "Default")
      (node (ref "Q1") (pin "B") (pinfunction "B_B") (pintype "passive"))
      (node (ref "R2") (pin "2") (pinfunction "2_2") (pintype "passive"))
    )
    (net (code "69") (name "Net-(Q2-PadB)") (class "Default")
      (node (ref "Q2") (pin "B") (pinfunction "B_B") (pintype "passive"))
      (node (ref "R5") (pin "1") (pinfunction "1_1") (pintype "passive"))
    )
    (net (code "70") (name "Net-(Q2-PadC)") (class "Default")
      (node (ref "Q2") (pin "C") (pinfunction "C_C") (pintype "passive"))
      (node (ref "R1") (pin "1") (pinfunction "1_1") (pintype "passive"))
    )
    (net (code "71") (name "Net-(Q3-G)") (class "Default")
      (node (ref "IC8") (pin "4") (pinfunction "4_4") (pintype "passive"))
      (node (ref "Q3") (pin "1") (pinfunction "G_1") (pintype "passive"))
      (node (ref "R10") (pin "1") (pinfunction "1_1") (pintype "passive"))
    )
    (net (code "72") (name "VBUS") (class "Default")
      (node (ref "D3") (pin "2") (pinfunction "A_2") (pintype "passive"))
      (node (ref "J3") (pin "VBUS") (pinfunction "VBUS_VBUS") (pintype "bidirectional"))
    )
    (net (code "73") (name "unconnected-(IC1D-O-Pad11)") (class "Default")
      (node (ref "IC1") (pin "11") (pinfunction "O_11") (pintype "tri_state"))
    )
    (net (code "74") (name "unconnected-(IC5-PA13(I2C{slash}SER2:1+)-Pad22)") (class "Default")
      (node (ref "IC5") (pin "22") (pinfunction "PA13(I2C/SER2:1+)_22") (pintype "bidirectional"))
    )
    (net (code "75") (name "unconnected-(IC5-PB03(AIN11{slash}SER5:1)-Pad48)") (class "Default")
      (node (ref "IC5") (pin "48") (pinfunction "PB03(AIN11/SER5:1)_48") (pintype "bidirectional"))
    )
    (net (code "76") (name "unconnected-(IC7-A7-Pad8)") (class "Default")
      (node (ref "IC7") (pin "8") (pinfunction "A7_8") (pintype "bidirectional"))
    )
    (net (code "77") (name "unconnected-(IC7-A8-Pad9)") (class "Default")
      (node (ref "IC7") (pin "9") (pinfunction "A8_9") (pintype "bidirectional"))
    )
    (net (code "78") (name "unconnected-(IC7-B7-Pad13)") (class "Default")
      (node (ref "IC7") (pin "13") (pinfunction "B7_13") (pintype "bidirectional"))
    )
    (net (code "79") (name "unconnected-(IC7-B8-Pad12)") (class "Default")
      (node (ref "IC7") (pin "12") (pinfunction "B8_12") (pintype "bidirectional"))
    )
    (net (code "80") (name "unconnected-(LCD1-DB0-Pad7)") (class "Default")
      (node (ref "LCD1") (pin "7") (pinfunction "DB0_7") (pintype "bidirectional"))
    )
    (net (code "81") (name "unconnected-(LCD1-DB1-Pad8)") (class "Default")
      (node (ref "LCD1") (pin "8") (pinfunction "DB1_8") (pintype "bidirectional"))
    )
    (net (code "82") (name "unconnected-(LCD1-DB2-Pad9)") (class "Default")
      (node (ref "LCD1") (pin "9") (pinfunction "DB2_9") (pintype "bidirectional"))
    )
    (net (code "83") (name "unconnected-(LCD1-DB3-Pad10)") (class "Default")
      (node (ref "LCD1") (pin "10") (pinfunction "DB3_10") (pintype "bidirectional"))
    )
    (net (code "84") (name "unconnected-(SD-DAT1-Pad8)") (class "Default")
      (node (ref "SD") (pin "8") (pinfunction "DAT1_8") (pintype "bidirectional"))
    )
    (net (code "85") (name "unconnected-(SD-DAT2-Pad1)") (class "Default")
      (node (ref "SD") (pin "1") (pinfunction "DAT2_1") (pintype "bidirectional"))
    )
    (net (code "86") (name "unconnected-(SD-DETECT-Pad9)") (class "Default")
      (node (ref "SD") (pin "9") (pinfunction "DETECT_9") (pintype "bidirectional"))
    )
  )
)
